# RiskChemi_Monitor_V1_04.net
KiCad netlist of a schematic drawn in Altium Designer
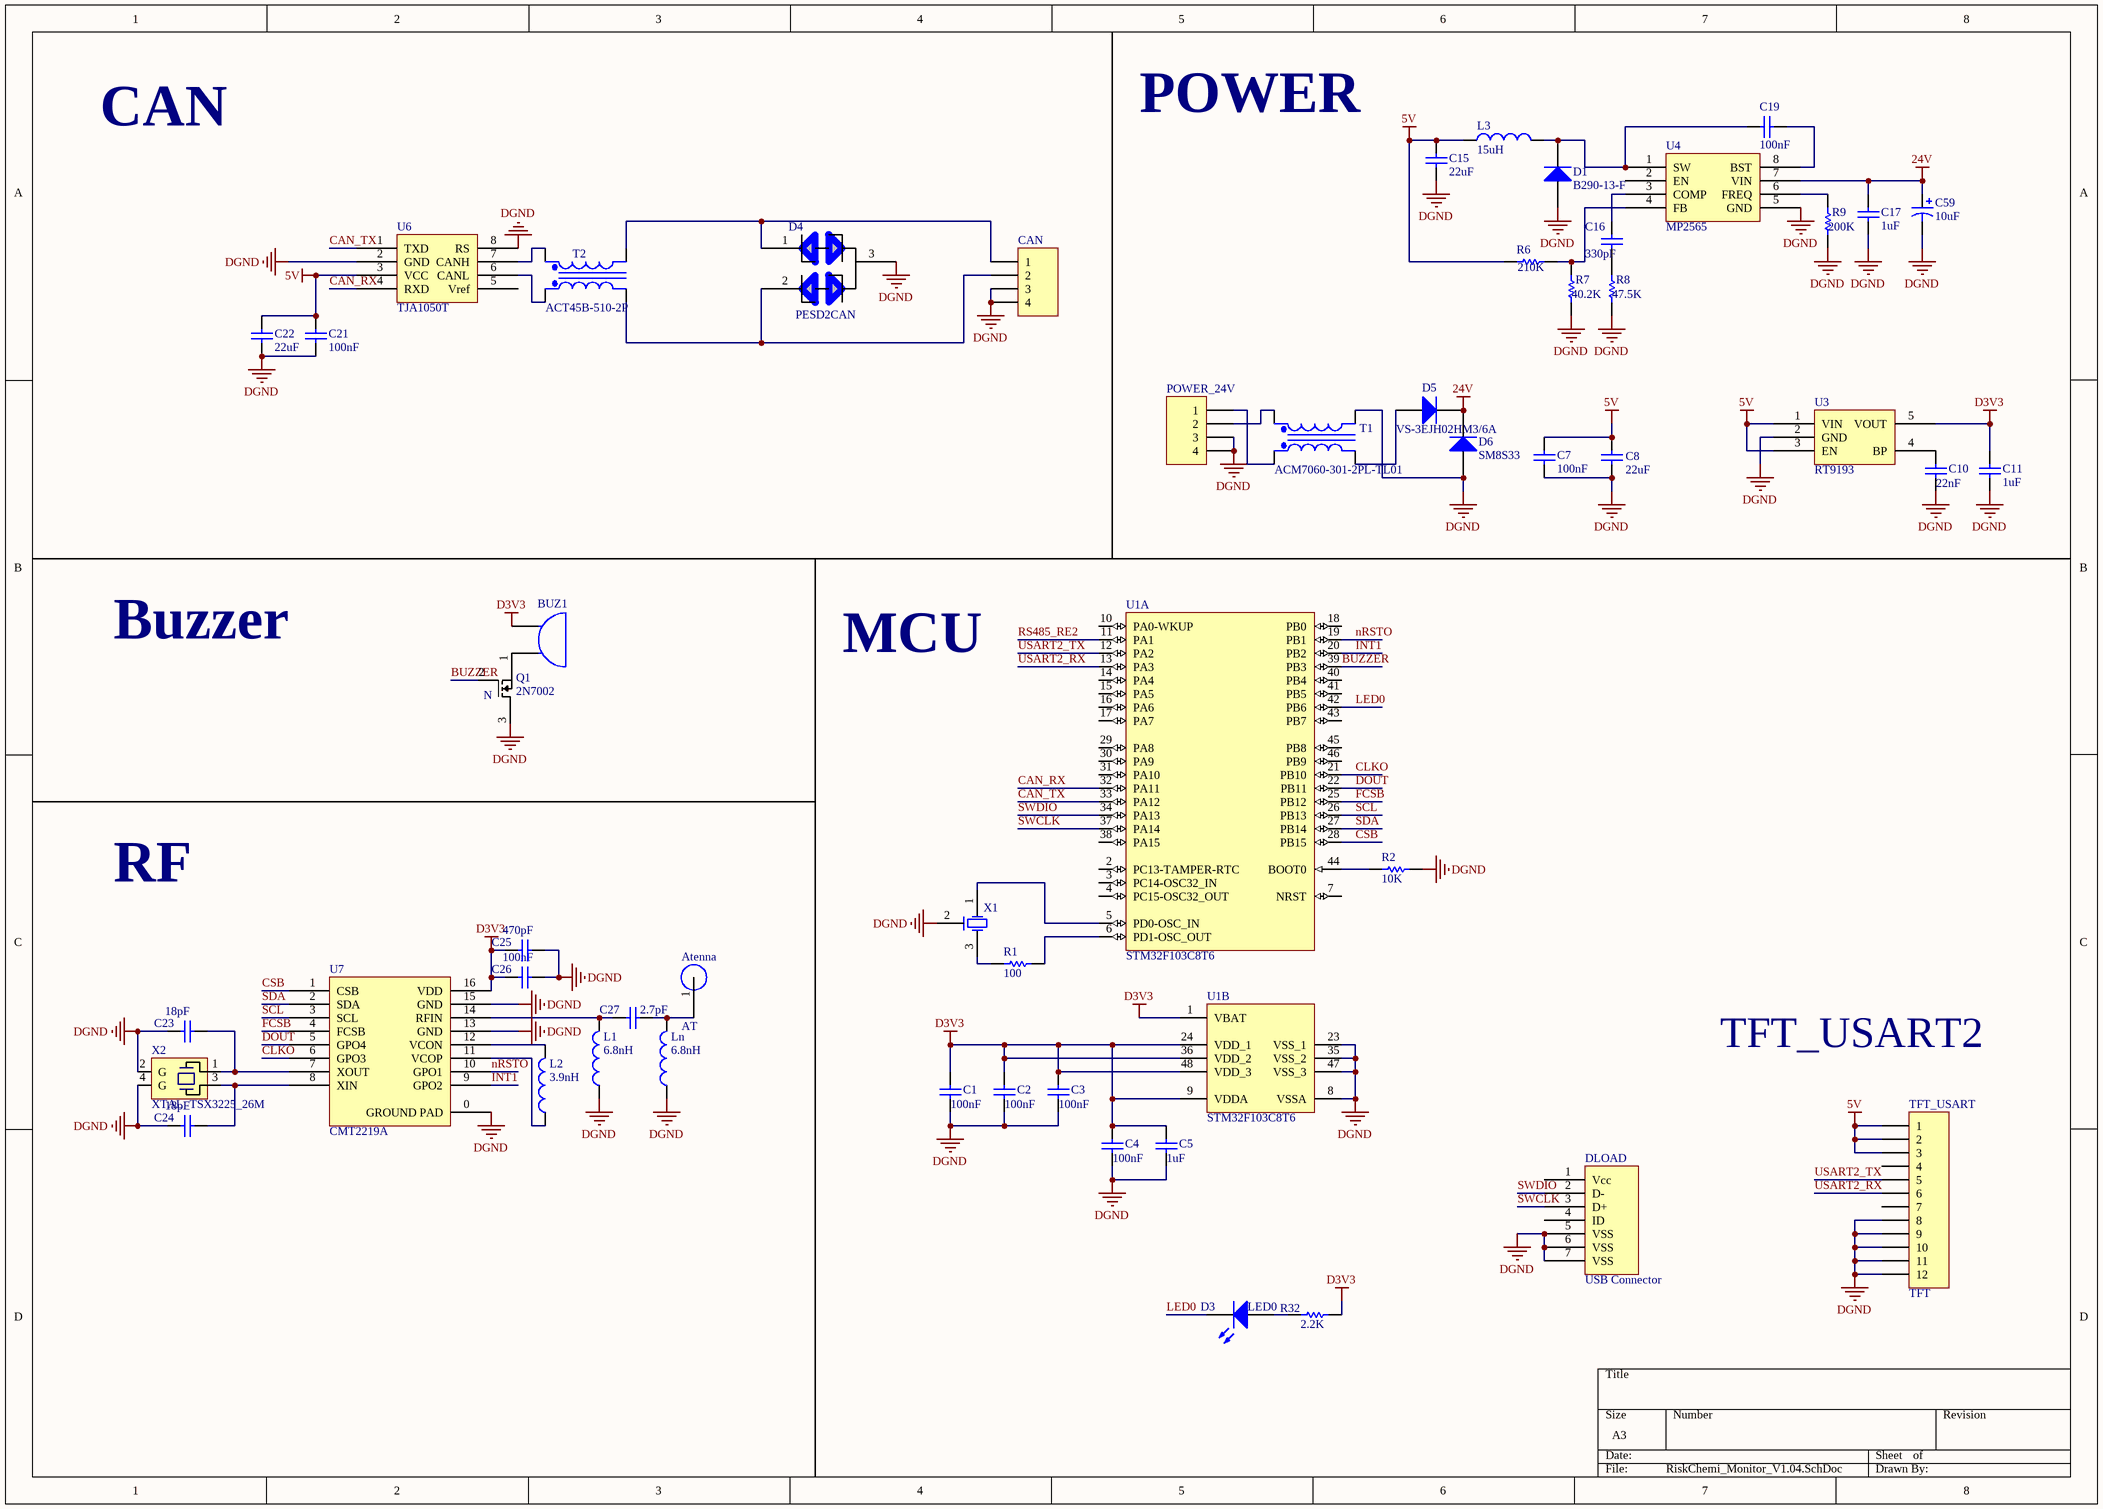
[diagram p0: RiskChemi_Monitor_V1.04.SchDoc]

(export (version "E")
  (design (tool "Eeschema 10.0.6"))
  (components
    (comp (ref "Atenna") (value "AT") (footprint "433MHz Atenna") (libsource (lib "MySchlib1") (part "AT")))
    (comp (ref "BUZ1")
      (value "BUZZER")
      (footprint "BUZ0905")
      (description "Buzzer")
      (libsource (lib "杂元件库") (part "BUZZER"))
    )
    (comp (ref "C1")
      (value "100nF")
      (footprint "0603")
      (description "Capacitor")
      (fields (field (name "PUBLISHER") "Altium Limited"))
      (libsource (lib "Miscellaneous Devices") (part "Cap"))
    )
    (comp (ref "C2")
      (value "100nF")
      (footprint "0603")
      (description "Capacitor")
      (fields (field (name "PUBLISHER") "Altium Limited"))
      (libsource (lib "Miscellaneous Devices") (part "Cap"))
    )
    (comp (ref "C3")
      (value "100nF")
      (footprint "0603")
      (description "Capacitor")
      (fields (field (name "PUBLISHER") "Altium Limited"))
      (libsource (lib "Miscellaneous Devices") (part "Cap"))
    )
    (comp (ref "C4")
      (value "100nF")
      (footprint "0603")
      (description "Capacitor")
      (fields (field (name "PUBLISHER") "Altium Limited"))
      (libsource (lib "Miscellaneous Devices") (part "Cap"))
    )
    (comp (ref "C5")
      (value "1uF")
      (footprint "0603")
      (description "Capacitor")
      (fields (field (name "PUBLISHER") "Altium Limited"))
      (libsource (lib "Miscellaneous Devices") (part "Cap"))
    )
    (comp (ref "C7")
      (value "100nF")
      (footprint "0805")
      (description "Capacitor,100V")
      (fields (field (name "PUBLISHER") "Altium Limited"))
      (libsource (lib "Miscellaneous Devices") (part "Cap"))
    )
    (comp (ref "C8")
      (value "22uF")
      (footprint "0805")
      (description "Capacitor")
      (fields (field (name "PUBLISHER") "Altium Limited"))
      (libsource (lib "Miscellaneous Devices") (part "Cap"))
    )
    (comp (ref "C10")
      (value "22nF")
      (footprint "BinFeng:0603")
      (description "Capacitor")
      (fields (field (name "PUBLISHER") "Altium Limited"))
      (libsource (lib "Miscellaneous Devices") (part "Cap"))
    )
    (comp (ref "C11")
      (value "1uF")
      (footprint "BinFeng:0603")
      (description "Capacitor")
      (fields (field (name "PUBLISHER") "Altium Limited"))
      (libsource (lib "Miscellaneous Devices") (part "Cap"))
    )
    (comp (ref "C15")
      (value "22uF")
      (footprint "0805")
      (description "Capacitor,50V")
      (fields (field (name "PUBLISHER") "Altium Limited"))
      (libsource (lib "Miscellaneous Devices") (part "Cap"))
    )
    (comp (ref "C16")
      (value "330pF")
      (footprint "BinFeng:0402")
      (description "Capacitor")
      (fields (field (name "PUBLISHER") "Altium Limited"))
      (libsource (lib "Miscellaneous Devices") (part "Cap"))
    )
    (comp (ref "C17")
      (value "1uF")
      (footprint "0805")
      (description "Capacitor,100V")
      (fields (field (name "PUBLISHER") "Altium Limited"))
      (libsource (lib "Miscellaneous Devices") (part "Cap"))
    )
    (comp (ref "C19")
      (value "100nF")
      (footprint "BinFeng:0402")
      (description "Capacitor")
      (fields (field (name "PUBLISHER") "Altium Limited"))
      (libsource (lib "Miscellaneous Devices") (part "Cap"))
    )
    (comp (ref "C21")
      (value "100nF")
      (footprint "0603")
      (description "Capacitor")
      (fields (field (name "PUBLISHER") "Altium Limited"))
      (libsource (lib "Miscellaneous Devices") (part "Cap"))
    )
    (comp (ref "C22")
      (value "22uF")
      (footprint "0805")
      (description "Capacitor")
      (fields (field (name "PUBLISHER") "Altium Limited"))
      (libsource (lib "Miscellaneous Devices") (part "Cap"))
    )
    (comp (ref "C23")
      (value "18pF")
      (footprint "BinFeng:0402")
      (description "Capacitor")
      (fields (field (name "PUBLISHER") "Altium Limited"))
      (libsource (lib "Miscellaneous Devices") (part "Cap"))
    )
    (comp (ref "C24")
      (value "18pF")
      (footprint "BinFeng:0402")
      (description "Capacitor")
      (fields (field (name "PUBLISHER") "Altium Limited"))
      (libsource (lib "Miscellaneous Devices") (part "Cap"))
    )
    (comp (ref "C25")
      (value "470pF")
      (footprint "BinFeng:0402")
      (description "Capacitor")
      (fields (field (name "PUBLISHER") "Altium Limited"))
      (libsource (lib "Miscellaneous Devices") (part "Cap"))
    )
    (comp (ref "C26")
      (value "100nF")
      (footprint "BinFeng:0603")
      (description "Capacitor")
      (fields (field (name "PUBLISHER") "Altium Limited"))
      (libsource (lib "Miscellaneous Devices") (part "Cap"))
    )
    (comp (ref "C27")
      (value "2.7pF")
      (footprint "BinFeng:nosilk_0402")
      (description "Capacitor")
      (fields (field (name "PUBLISHER") "Altium Limited"))
      (libsource (lib "Miscellaneous Devices") (part "Cap"))
    )
    (comp (ref "C59")
      (value "10uF")
      (footprint "6032_pol")
      (description "Polarized Capacitor (Radial)")
      (fields (field (name "PUBLISHER") "Altium Limited"))
      (libsource (lib "Miscellaneous Devices") (part "Cap Pol1"))
    )
    (comp (ref "CAN")
      (value "Header 4")
      (footprint "C3000VS")
      (description "Header, 4-Pin")
      (fields (field (name "PUBLISHER") "Altium Limited"))
      (libsource (lib "") (part "Header 4_1"))
    )
    (comp (ref "D1")
      (value "B290-13-F")
      (footprint "back:B290")
      (description "Default Diode")
      (fields (field (name "PUBLISHER") "Altium Limited"))
      (libsource (lib "Miscellaneous Devices") (part "Diode"))
    )
    (comp (ref "D3")
      (value "LED0")
      (footprint "LED")
      (description "green LED")
      (fields (field (name "PUBLISHER") "Altium Limited"))
      (libsource (lib "Miscellaneous Devices") (part "LED0"))
    )
    (comp (ref "D4")
      (value "PESD2CAN")
      (footprint "SOT23")
      (libsource (lib "BinFeng_Connectors") (part "PESD1CAN"))
    )
    (comp (ref "D5")
      (value "VS-3EJH02HM3/6A")
      (footprint "back:B290")
      (description "1 Amp General Purpose Rectifier")
      (fields (field (name "PUBLISHER") "Altium Limited"))
      (libsource (lib "Miscellaneous Devices") (part "Diode 1N4007"))
    )
    (comp (ref "D6")
      (value "SM8S33")
      (footprint "SM8S")
      (description "1 Amp General Purpose Rectifier")
      (fields (field (name "PUBLISHER") "Altium Limited"))
      (libsource (lib "Miscellaneous Devices") (part "Diode 1N4007"))
    )
    (comp (ref "DLOAD")
      (value "USB Connector")
      (footprint "Mini_USB")
      (libsource (lib "BinFeng_Connectors") (part "Component_1"))
    )
    (comp (ref "L1")
      (value "6.8nH")
      (footprint "Miscellaneous Devices:0402")
      (description "Inductor")
      (fields (field (name "PUBLISHER") "Altium Limited"))
      (libsource (lib "Miscellaneous Devices") (part "Inductor"))
    )
    (comp (ref "L2")
      (value "3.9nH")
      (footprint "BinFeng:0603")
      (description "Inductor")
      (fields (field (name "PUBLISHER") "Altium Limited"))
      (libsource (lib "Miscellaneous Devices") (part "Inductor"))
    )
    (comp (ref "L3")
      (value "15uH")
      (footprint "4*4 Inductor")
      (description "Inductor, 1A")
      (fields (field (name "PUBLISHER") "Altium Limited"))
      (libsource (lib "Miscellaneous Devices") (part "Inductor"))
    )
    (comp (ref "Ln")
      (value "6.8nH")
      (footprint "Miscellaneous Devices:0402")
      (description "Inductor")
      (fields (field (name "PUBLISHER") "Altium Limited"))
      (libsource (lib "Miscellaneous Devices") (part "Inductor"))
    )
    (comp (ref "POWER_24V")
      (value "Header 4")
      (footprint "C3000VS")
      (description "Header, 4-Pin")
      (fields (field (name "PUBLISHER") "Altium Limited"))
      (libsource (lib "Miscellaneous Connectors") (part "Header 4"))
    )
    (comp (ref "Q1") (value "2N7002") (footprint "2N7002") (libsource (lib "seeder") (part "N-MOSFET")))
    (comp (ref "R1")
      (value "100")
      (footprint "back:0603")
      (description "Resistor")
      (fields (field (name "PUBLISHER") "Altium Limited"))
      (libsource (lib "Miscellaneous Devices") (part "Res1"))
    )
    (comp (ref "R2")
      (value "10K")
      (footprint "back:0603")
      (description "Resistor")
      (fields (field (name "PUBLISHER") "Altium Limited"))
      (libsource (lib "Miscellaneous Devices") (part "Res1"))
    )
    (comp (ref "R6")
      (value "210K")
      (footprint "BinFeng:0402")
      (description "Resistor")
      (fields (field (name "PUBLISHER") "Altium Limited"))
      (libsource (lib "Miscellaneous Devices") (part "Res1"))
    )
    (comp (ref "R7")
      (value "40.2K")
      (footprint "BinFeng:0402")
      (description "Resistor")
      (fields (field (name "PUBLISHER") "Altium Limited"))
      (libsource (lib "Miscellaneous Devices") (part "Res1"))
    )
    (comp (ref "R8")
      (value "47.5K")
      (footprint "BinFeng:0402")
      (description "Resistor")
      (fields (field (name "PUBLISHER") "Altium Limited"))
      (libsource (lib "Miscellaneous Devices") (part "Res1"))
    )
    (comp (ref "R9")
      (value "200K")
      (footprint "BinFeng:0402")
      (description "Resistor")
      (fields (field (name "PUBLISHER") "Altium Limited"))
      (libsource (lib "Miscellaneous Devices") (part "Res1"))
    )
    (comp (ref "R32")
      (value "2.2K")
      (footprint "BinFeng:0603")
      (description "Resistor")
      (fields (field (name "PUBLISHER") "Altium Limited"))
      (libsource (lib "Miscellaneous Devices") (part "Res1"))
    )
    (comp (ref "T1")
      (value "ACM7060-301-2PL-TL01")
      (footprint "ACM7060-301-2P-TL01")
      (description "Transformer (Equivalent Circuit Model)")
      (fields (field (name "PUBLISHER") "Altium Limited"))
      (libsource (lib "Miscellaneous Devices") (part "Trans Eq"))
    )
    (comp (ref "T2")
      (value "ACT45B-510-2P")
      (footprint "ACT45B-510-2P")
      (description "Transformer (Equivalent Circuit Model)")
      (fields (field (name "PUBLISHER") "Altium Limited"))
      (libsource (lib "Miscellaneous Devices") (part "Trans Eq"))
    )
    (comp (ref "TFT_USART")
      (value "TFT")
      (footprint "FCC_10pin_1mm")
      (description "Header, 12-Pin")
      (fields (field (name "PUBLISHER") "Altium Limited"))
      (libsource (lib "Miscellaneous Connectors") (part "Header 12"))
    )
    (comp (ref "U1")
      (value "STM32F103C8T6")
      (footprint "STM-LQFP48_N")
      (libsource (lib "STMicroelectronics STM32 F1") (part "STM32F103C8T6"))
    )
    (comp (ref "U3") (value "RT9193") (footprint "SOT-23-5") (libsource (lib "BinFeng_IC") (part "RT9193")))
    (comp (ref "U4")
      (value "MP2565")
      (footprint "SO8")
      (description "DCDC 4.5V~28V input 1.8V ~5V output low power")
      (libsource (lib "BinFeng_IC") (part "MP1584"))
    )
    (comp (ref "U6")
      (value "TJA1050T")
      (footprint "SO8")
      (description "CAN Tranceiver")
      (libsource (lib "BinFeng_IC") (part "TJA1050T"))
    )
    (comp (ref "U7")
      (value "CMT2219A")
      (footprint "back:QFN16")
      (libsource (lib "BinFeng_IC") (part "CMT2219A"))
    )
    (comp (ref "X1") (value "8M smd") (footprint "8Mhz_XTAL") (libsource (lib "Schlib1") (part "8M smd")))
    (comp (ref "X2")
      (value "XTAL_TSX3225_26M")
      (footprint "XTAL3225")
      (libsource (lib "BinFeng_IC") (part "XTAL_Negative"))
    )
  )
  (nets
    (net (code "1") (name "/BUZZER") (class "Default")
      (node (ref "Q1") (pin "2") (pinfunction "G_2") (pintype "passive"))
      (node (ref "U1") (pin "39") (pinfunction "PB3_39") (pintype "bidirectional"))
    )
    (net (code "2") (name "/CAN_RX") (class "Default")
      (node (ref "U1") (pin "32") (pinfunction "PA11_32") (pintype "bidirectional"))
      (node (ref "U6") (pin "4") (pinfunction "RXD_4") (pintype "passive"))
    )
    (net (code "3") (name "/CAN_TX") (class "Default")
      (node (ref "U1") (pin "33") (pinfunction "PA12_33") (pintype "bidirectional"))
      (node (ref "U6") (pin "1") (pinfunction "TXD_1") (pintype "passive"))
    )
    (net (code "4") (name "/CLKO") (class "Default")
      (node (ref "U1") (pin "21") (pinfunction "PB10_21") (pintype "bidirectional"))
      (node (ref "U7") (pin "6") (pinfunction "GPO3_6") (pintype "passive"))
    )
    (net (code "5") (name "/CSB") (class "Default")
      (node (ref "U1") (pin "28") (pinfunction "PB15_28") (pintype "bidirectional"))
      (node (ref "U7") (pin "1") (pinfunction "CSB_1") (pintype "passive"))
    )
    (net (code "6") (name "/DOUT") (class "Default")
      (node (ref "U1") (pin "22") (pinfunction "PB11_22") (pintype "bidirectional"))
      (node (ref "U7") (pin "5") (pinfunction "GPO4_5") (pintype "passive"))
    )
    (net (code "7") (name "/FCSB") (class "Default")
      (node (ref "U1") (pin "25") (pinfunction "PB12_25") (pintype "bidirectional"))
      (node (ref "U7") (pin "4") (pinfunction "FCSB_4") (pintype "passive"))
    )
    (net (code "8") (name "/INT1") (class "Default")
      (node (ref "U1") (pin "20") (pinfunction "PB2_20") (pintype "bidirectional"))
      (node (ref "U7") (pin "9") (pinfunction "GPO2_9") (pintype "passive"))
    )
    (net (code "9") (name "/LED0") (class "Default")
      (node (ref "D3") (pin "2") (pinfunction "K_2") (pintype "passive"))
      (node (ref "U1") (pin "42") (pinfunction "PB6_42") (pintype "bidirectional"))
    )
    (net (code "10") (name "/RS485_RE2") (class "Default")
      (node (ref "U1") (pin "11") (pinfunction "PA1_11") (pintype "bidirectional"))
    )
    (net (code "11") (name "/SCL") (class "Default")
      (node (ref "U1") (pin "26") (pinfunction "PB13_26") (pintype "bidirectional"))
      (node (ref "U7") (pin "3") (pinfunction "SCL_3") (pintype "passive"))
    )
    (net (code "12") (name "/SDA") (class "Default")
      (node (ref "U1") (pin "27") (pinfunction "PB14_27") (pintype "bidirectional"))
      (node (ref "U7") (pin "2") (pinfunction "SDA_2") (pintype "passive"))
    )
    (net (code "13") (name "/SWCLK") (class "Default")
      (node (ref "DLOAD") (pin "3") (pinfunction "D+_3") (pintype "passive"))
      (node (ref "U1") (pin "37") (pinfunction "PA14_37") (pintype "bidirectional"))
    )
    (net (code "14") (name "/SWDIO") (class "Default")
      (node (ref "DLOAD") (pin "2") (pinfunction "D-_2") (pintype "passive"))
      (node (ref "U1") (pin "34") (pinfunction "PA13_34") (pintype "bidirectional"))
    )
    (net (code "15") (name "/USART2_RX") (class "Default")
      (node (ref "TFT_USART") (pin "6") (pinfunction "6_6") (pintype "passive"))
      (node (ref "U1") (pin "13") (pinfunction "PA3_13") (pintype "bidirectional"))
    )
    (net (code "16") (name "/USART2_TX") (class "Default")
      (node (ref "TFT_USART") (pin "5") (pinfunction "5_5") (pintype "passive"))
      (node (ref "U1") (pin "12") (pinfunction "PA2_12") (pintype "bidirectional"))
    )
    (net (code "17") (name "/nRSTO") (class "Default")
      (node (ref "U1") (pin "19") (pinfunction "PB1_19") (pintype "bidirectional"))
      (node (ref "U7") (pin "10") (pinfunction "GPO1_10") (pintype "passive"))
    )
    (net (code "18") (name "5V") (class "Default")
      (node (ref "C15") (pin "2") (pinfunction "2_2") (pintype "passive"))
      (node (ref "C21") (pin "1") (pinfunction "1_1") (pintype "passive"))
      (node (ref "C22") (pin "2") (pinfunction "2_2") (pintype "passive"))
      (node (ref "C7") (pin "2") (pinfunction "2_2") (pintype "passive"))
      (node (ref "C8") (pin "2") (pinfunction "2_2") (pintype "passive"))
      (node (ref "L3") (pin "1") (pinfunction "1_1") (pintype "passive"))
      (node (ref "R6") (pin "2") (pinfunction "2_2") (pintype "passive"))
      (node (ref "TFT_USART") (pin "1") (pinfunction "1_1") (pintype "passive"))
      (node (ref "TFT_USART") (pin "2") (pinfunction "2_2") (pintype "passive"))
      (node (ref "TFT_USART") (pin "3") (pinfunction "3_3") (pintype "passive"))
      (node (ref "U3") (pin "1") (pinfunction "VIN_1") (pintype "passive"))
      (node (ref "U3") (pin "3") (pinfunction "EN_3") (pintype "passive"))
      (node (ref "U6") (pin "3") (pinfunction "VCC_3") (pintype "passive"))
    )
    (net (code "19") (name "24V") (class "Default")
      (node (ref "C17") (pin "2") (pinfunction "2_2") (pintype "passive"))
      (node (ref "C59") (pin "1") (pinfunction "1_1") (pintype "passive"))
      (node (ref "D5") (pin "2") (pinfunction "K_2") (pintype "passive"))
      (node (ref "D6") (pin "2") (pinfunction "K_2") (pintype "passive"))
      (node (ref "U4") (pin "7") (pinfunction "VIN_7") (pintype "passive"))
    )
    (net (code "20") (name "D3V3") (class "Default")
      (node (ref "BUZ1") (pin "1") (pinfunction "A_1") (pintype "passive"))
      (node (ref "C1") (pin "2") (pinfunction "2_2") (pintype "passive"))
      (node (ref "C11") (pin "2") (pinfunction "2_2") (pintype "passive"))
      (node (ref "C2") (pin "2") (pinfunction "2_2") (pintype "passive"))
      (node (ref "C25") (pin "2") (pinfunction "2_2") (pintype "passive"))
      (node (ref "C26") (pin "2") (pinfunction "2_2") (pintype "passive"))
      (node (ref "C3") (pin "2") (pinfunction "2_2") (pintype "passive"))
      (node (ref "C4") (pin "2") (pinfunction "2_2") (pintype "passive"))
      (node (ref "C5") (pin "2") (pinfunction "2_2") (pintype "passive"))
      (node (ref "R32") (pin "1") (pinfunction "1_1") (pintype "passive"))
      (node (ref "U1") (pin "1") (pinfunction "VBAT_1") (pintype "power_in"))
      (node (ref "U1") (pin "24") (pinfunction "VDD_1_24") (pintype "power_in"))
      (node (ref "U1") (pin "36") (pinfunction "VDD_2_36") (pintype "power_in"))
      (node (ref "U1") (pin "48") (pinfunction "VDD_3_48") (pintype "power_in"))
      (node (ref "U1") (pin "9") (pinfunction "VDDA_9") (pintype "power_in"))
      (node (ref "U3") (pin "5") (pinfunction "VOUT_5") (pintype "passive"))
      (node (ref "U7") (pin "16") (pinfunction "VDD_16") (pintype "passive"))
    )
    (net (code "21") (name "DGND") (class "Default")
      (node (ref "C1") (pin "1") (pinfunction "1_1") (pintype "passive"))
      (node (ref "C10") (pin "1") (pinfunction "1_1") (pintype "passive"))
      (node (ref "C11") (pin "1") (pinfunction "1_1") (pintype "passive"))
      (node (ref "C15") (pin "1") (pinfunction "1_1") (pintype "passive"))
      (node (ref "C17") (pin "1") (pinfunction "1_1") (pintype "passive"))
      (node (ref "C2") (pin "1") (pinfunction "1_1") (pintype "passive"))
      (node (ref "C21") (pin "2") (pinfunction "2_2") (pintype "passive"))
      (node (ref "C22") (pin "1") (pinfunction "1_1") (pintype "passive"))
      (node (ref "C23") (pin "2") (pinfunction "2_2") (pintype "passive"))
      (node (ref "C24") (pin "2") (pinfunction "2_2") (pintype "passive"))
      (node (ref "C25") (pin "1") (pinfunction "1_1") (pintype "passive"))
      (node (ref "C26") (pin "1") (pinfunction "1_1") (pintype "passive"))
      (node (ref "C3") (pin "1") (pinfunction "1_1") (pintype "passive"))
      (node (ref "C4") (pin "1") (pinfunction "1_1") (pintype "passive"))
      (node (ref "C5") (pin "1") (pinfunction "1_1") (pintype "passive"))
      (node (ref "C59") (pin "2") (pinfunction "2_2") (pintype "passive"))
      (node (ref "C7") (pin "1") (pinfunction "1_1") (pintype "passive"))
      (node (ref "C8") (pin "1") (pinfunction "1_1") (pintype "passive"))
      (node (ref "CAN") (pin "3") (pinfunction "3_3") (pintype "passive"))
      (node (ref "CAN") (pin "4") (pinfunction "4_4") (pintype "passive"))
      (node (ref "D1") (pin "1") (pinfunction "A_1") (pintype "passive"))
      (node (ref "D4") (pin "3") (pinfunction "13_3") (pintype "passive"))
      (node (ref "D6") (pin "1") (pinfunction "A_1") (pintype "passive"))
      (node (ref "DLOAD") (pin "5") (pinfunction "VSS_5") (pintype "passive"))
      (node (ref "DLOAD") (pin "6") (pinfunction "VSS_6") (pintype "passive"))
      (node (ref "DLOAD") (pin "7") (pinfunction "VSS_7") (pintype "passive"))
      (node (ref "L1") (pin "1") (pinfunction "1_1") (pintype "passive"))
      (node (ref "Ln") (pin "1") (pinfunction "1_1") (pintype "passive"))
      (node (ref "POWER_24V") (pin "3") (pinfunction "3_3") (pintype "passive"))
      (node (ref "POWER_24V") (pin "4") (pinfunction "4_4") (pintype "passive"))
      (node (ref "Q1") (pin "3") (pinfunction "S_3") (pintype "passive"))
      (node (ref "R2") (pin "2") (pinfunction "2_2") (pintype "passive"))
      (node (ref "R7") (pin "1") (pinfunction "1_1") (pintype "passive"))
      (node (ref "R8") (pin "1") (pinfunction "1_1") (pintype "passive"))
      (node (ref "R9") (pin "1") (pinfunction "1_1") (pintype "passive"))
      (node (ref "T1") (pin "4") (pinfunction "Sec-_4") (pintype "passive"))
      (node (ref "TFT_USART") (pin "10") (pinfunction "10_10") (pintype "passive"))
      (node (ref "TFT_USART") (pin "11") (pinfunction "11_11") (pintype "passive"))
      (node (ref "TFT_USART") (pin "12") (pinfunction "12_12") (pintype "passive"))
      (node (ref "TFT_USART") (pin "8") (pinfunction "8_8") (pintype "passive"))
      (node (ref "TFT_USART") (pin "9") (pinfunction "9_9") (pintype "passive"))
      (node (ref "U1") (pin "23") (pinfunction "VSS_1_23") (pintype "power_in"))
      (node (ref "U1") (pin "35") (pinfunction "VSS_2_35") (pintype "power_in"))
      (node (ref "U1") (pin "47") (pinfunction "VSS_3_47") (pintype "power_in"))
      (node (ref "U1") (pin "8") (pinfunction "VSSA_8") (pintype "power_in"))
      (node (ref "U3") (pin "2") (pinfunction "GND_2") (pintype "passive"))
      (node (ref "U4") (pin "5") (pinfunction "GND_5") (pintype "passive"))
      (node (ref "U6") (pin "2") (pinfunction "GND_2") (pintype "passive"))
      (node (ref "U6") (pin "8") (pinfunction "RS_8") (pintype "passive"))
      (node (ref "U7") (pin "0") (pinfunction "GROUND_PAD_0") (pintype "passive"))
      (node (ref "U7") (pin "13") (pinfunction "GND_13") (pintype "passive"))
      (node (ref "U7") (pin "15") (pinfunction "GND_15") (pintype "passive"))
      (node (ref "X1") (pin "2") (pinfunction "GND_2") (pintype "passive"))
      (node (ref "X2") (pin "2") (pinfunction "G_2") (pintype "passive"))
      (node (ref "X2") (pin "4") (pinfunction "G_4") (pintype "passive"))
    )
    (net (code "22") (name "Net-(Atenna-Pad1)") (class "Default")
      (node (ref "Atenna") (pin "1") (pinfunction "1_1") (pintype "passive"))
      (node (ref "C27") (pin "1") (pinfunction "1_1") (pintype "passive"))
      (node (ref "Ln") (pin "2") (pinfunction "2_2") (pintype "passive"))
    )
    (net (code "23") (name "Net-(BUZ1-B)") (class "Default")
      (node (ref "BUZ1") (pin "2") (pinfunction "B_2") (pintype "passive"))
      (node (ref "Q1") (pin "1") (pinfunction "D_1") (pintype "passive"))
    )
    (net (code "24") (name "Net-(C16-Pad2)") (class "Default")
      (node (ref "C16") (pin "2") (pinfunction "2_2") (pintype "passive"))
      (node (ref "R8") (pin "2") (pinfunction "2_2") (pintype "passive"))
    )
    (net (code "25") (name "Net-(D1-K)") (class "Default")
      (node (ref "C19") (pin "2") (pinfunction "2_2") (pintype "passive"))
      (node (ref "D1") (pin "2") (pinfunction "K_2") (pintype "passive"))
      (node (ref "L3") (pin "2") (pinfunction "2_2") (pintype "passive"))
      (node (ref "U4") (pin "1") (pinfunction "SW_1") (pintype "passive"))
    )
    (net (code "26") (name "Net-(D3-A)") (class "Default")
      (node (ref "D3") (pin "1") (pinfunction "A_1") (pintype "passive"))
      (node (ref "R32") (pin "2") (pinfunction "2_2") (pintype "passive"))
    )
    (net (code "27") (name "Net-(D4-11)") (class "Default")
      (node (ref "CAN") (pin "1") (pinfunction "1_1") (pintype "passive"))
      (node (ref "D4") (pin "1") (pinfunction "11_1") (pintype "passive"))
      (node (ref "T2") (pin "4") (pinfunction "Sec-_4") (pintype "passive"))
    )
    (net (code "28") (name "Net-(D4-12)") (class "Default")
      (node (ref "CAN") (pin "2") (pinfunction "2_2") (pintype "passive"))
      (node (ref "D4") (pin "2") (pinfunction "12_2") (pintype "passive"))
      (node (ref "T2") (pin "2") (pinfunction "Pri-_2") (pintype "passive"))
    )
    (net (code "29") (name "Net-(D5-A)") (class "Default")
      (node (ref "D5") (pin "1") (pinfunction "A_1") (pintype "passive"))
      (node (ref "T1") (pin "2") (pinfunction "Pri-_2") (pintype "passive"))
    )
    (net (code "30") (name "Net-(T1-Pri+)") (class "Default")
      (node (ref "POWER_24V") (pin "1") (pinfunction "1_1") (pintype "passive"))
      (node (ref "T1") (pin "1") (pinfunction "Pri+_1") (pintype "passive"))
    )
    (net (code "31") (name "Net-(T1-Sec+)") (class "Default")
      (node (ref "POWER_24V") (pin "2") (pinfunction "2_2") (pintype "passive"))
      (node (ref "T1") (pin "3") (pinfunction "Sec+_3") (pintype "passive"))
    )
    (net (code "32") (name "Net-(T2-Pri+)") (class "Default")
      (node (ref "T2") (pin "1") (pinfunction "Pri+_1") (pintype "passive"))
      (node (ref "U6") (pin "6") (pinfunction "CANL_6") (pintype "passive"))
    )
    (net (code "33") (name "Net-(T2-Sec+)") (class "Default")
      (node (ref "T2") (pin "3") (pinfunction "Sec+_3") (pintype "passive"))
      (node (ref "U6") (pin "7") (pinfunction "CANH_7") (pintype "passive"))
    )
    (net (code "34") (name "Net-(U1A-BOOT0)") (class "Default")
      (node (ref "R2") (pin "1") (pinfunction "1_1") (pintype "passive"))
      (node (ref "U1") (pin "44") (pinfunction "BOOT0_44") (pintype "input"))
    )
    (net (code "35") (name "Net-(U1A-PD0-OSC_IN)") (class "Default")
      (node (ref "U1") (pin "5") (pinfunction "PD0-OSC_IN_5") (pintype "bidirectional"))
      (node (ref "X1") (pin "1") (pinfunction "OSC1_1") (pintype "passive"))
    )
    (net (code "36") (name "Net-(U1A-PD1-OSC_OUT)") (class "Default")
      (node (ref "R1") (pin "2") (pinfunction "2_2") (pintype "passive"))
      (node (ref "U1") (pin "6") (pinfunction "PD1-OSC_OUT_6") (pintype "bidirectional"))
    )
    (net (code "37") (name "Net-(U3-BP)") (class "Default")
      (node (ref "C10") (pin "2") (pinfunction "2_2") (pintype "passive"))
      (node (ref "U3") (pin "4") (pinfunction "BP_4") (pintype "passive"))
    )
    (net (code "38") (name "Net-(U4-BST)") (class "Default")
      (node (ref "C19") (pin "1") (pinfunction "1_1") (pintype "passive"))
      (node (ref "U4") (pin "8") (pinfunction "BST_8") (pintype "passive"))
    )
    (net (code "39") (name "Net-(U4-COMP)") (class "Default")
      (node (ref "C16") (pin "1") (pinfunction "1_1") (pintype "passive"))
      (node (ref "U4") (pin "3") (pinfunction "COMP_3") (pintype "passive"))
    )
    (net (code "40") (name "Net-(U4-FB)") (class "Default")
      (node (ref "R6") (pin "1") (pinfunction "1_1") (pintype "passive"))
      (node (ref "R7") (pin "2") (pinfunction "2_2") (pintype "passive"))
      (node (ref "U4") (pin "4") (pinfunction "FB_4") (pintype "passive"))
    )
    (net (code "41") (name "Net-(U4-FREQ)") (class "Default")
      (node (ref "R9") (pin "2") (pinfunction "2_2") (pintype "passive"))
      (node (ref "U4") (pin "6") (pinfunction "FREQ_6") (pintype "passive"))
    )
    (net (code "42") (name "Net-(U7-RFIN)") (class "Default")
      (node (ref "C27") (pin "2") (pinfunction "2_2") (pintype "passive"))
      (node (ref "L1") (pin "2") (pinfunction "2_2") (pintype "passive"))
      (node (ref "U7") (pin "14") (pinfunction "RFIN_14") (pintype "passive"))
    )
    (net (code "43") (name "Net-(U7-VCON)") (class "Default")
      (node (ref "L2") (pin "2") (pinfunction "2_2") (pintype "passive"))
      (node (ref "U7") (pin "12") (pinfunction "VCON_12") (pintype "passive"))
    )
    (net (code "44") (name "Net-(U7-VCOP)") (class "Default")
      (node (ref "L2") (pin "1") (pinfunction "1_1") (pintype "passive"))
      (node (ref "U7") (pin "11") (pinfunction "VCOP_11") (pintype "passive"))
    )
    (net (code "45") (name "Net-(U7-XIN)") (class "Default")
      (node (ref "C24") (pin "1") (pinfunction "1_1") (pintype "passive"))
      (node (ref "U7") (pin "8") (pinfunction "XIN_8") (pintype "passive"))
      (node (ref "X2") (pin "3") (pintype "passive"))
    )
    (net (code "46") (name "Net-(U7-XOUT)") (class "Default")
      (node (ref "C23") (pin "1") (pinfunction "1_1") (pintype "passive"))
      (node (ref "U7") (pin "7") (pinfunction "XOUT_7") (pintype "passive"))
      (node (ref "X2") (pin "1") (pintype "passive"))
    )
    (net (code "47") (name "Net-(X1-OSC2)") (class "Default")
      (node (ref "R1") (pin "1") (pinfunction "1_1") (pintype "passive"))
      (node (ref "X1") (pin "3") (pinfunction "OSC2_3") (pintype "passive"))
    )
    (net (code "48") (name "unconnected-(DLOAD-ID-Pad4)") (class "Default")
      (node (ref "DLOAD") (pin "4") (pinfunction "ID_4") (pintype "passive"))
    )
    (net (code "49") (name "unconnected-(DLOAD-Vcc-Pad1)") (class "Default")
      (node (ref "DLOAD") (pin "1") (pinfunction "Vcc_1") (pintype "passive"))
    )
    (net (code "50") (name "unconnected-(TFT_USART-Pad4)") (class "Default")
      (node (ref "TFT_USART") (pin "4") (pinfunction "4_4") (pintype "passive"))
    )
    (net (code "51") (name "unconnected-(TFT_USART-Pad7)") (class "Default")
      (node (ref "TFT_USART") (pin "7") (pinfunction "7_7") (pintype "passive"))
    )
    (net (code "52") (name "unconnected-(U1A-NRST-Pad7)") (class "Default")
      (node (ref "U1") (pin "7") (pinfunction "NRST_7") (pintype "bidirectional"))
    )
    (net (code "53") (name "unconnected-(U1A-PA0-WKUP-Pad10)") (class "Default")
      (node (ref "U1") (pin "10") (pinfunction "PA0-WKUP_10") (pintype "bidirectional"))
    )
    (net (code "54") (name "unconnected-(U1A-PA4-Pad14)") (class "Default")
      (node (ref "U1") (pin "14") (pinfunction "PA4_14") (pintype "bidirectional"))
    )
    (net (code "55") (name "unconnected-(U1A-PA5-Pad15)") (class "Default")
      (node (ref "U1") (pin "15") (pinfunction "PA5_15") (pintype "bidirectional"))
    )
    (net (code "56") (name "unconnected-(U1A-PA6-Pad16)") (class "Default")
      (node (ref "U1") (pin "16") (pinfunction "PA6_16") (pintype "bidirectional"))
    )
    (net (code "57") (name "unconnected-(U1A-PA7-Pad17)") (class "Default")
      (node (ref "U1") (pin "17") (pinfunction "PA7_17") (pintype "bidirectional"))
    )
    (net (code "58") (name "unconnected-(U1A-PA8-Pad29)") (class "Default")
      (node (ref "U1") (pin "29") (pinfunction "PA8_29") (pintype "bidirectional"))
    )
    (net (code "59") (name "unconnected-(U1A-PA9-Pad30)") (class "Default")
      (node (ref "U1") (pin "30") (pinfunction "PA9_30") (pintype "bidirectional"))
    )
    (net (code "60") (name "unconnected-(U1A-PA10-Pad31)") (class "Default")
      (node (ref "U1") (pin "31") (pinfunction "PA10_31") (pintype "bidirectional"))
    )
    (net (code "61") (name "unconnected-(U1A-PA15-Pad38)") (class "Default")
      (node (ref "U1") (pin "38") (pinfunction "PA15_38") (pintype "bidirectional"))
    )
    (net (code "62") (name "unconnected-(U1A-PB0-Pad18)") (class "Default")
      (node (ref "U1") (pin "18") (pinfunction "PB0_18") (pintype "bidirectional"))
    )
    (net (code "63") (name "unconnected-(U1A-PB4-Pad40)") (class "Default")
      (node (ref "U1") (pin "40") (pinfunction "PB4_40") (pintype "bidirectional"))
    )
    (net (code "64") (name "unconnected-(U1A-PB5-Pad41)") (class "Default")
      (node (ref "U1") (pin "41") (pinfunction "PB5_41") (pintype "bidirectional"))
    )
    (net (code "65") (name "unconnected-(U1A-PB7-Pad43)") (class "Default")
      (node (ref "U1") (pin "43") (pinfunction "PB7_43") (pintype "bidirectional"))
    )
    (net (code "66") (name "unconnected-(U1A-PB8-Pad45)") (class "Default")
      (node (ref "U1") (pin "45") (pinfunction "PB8_45") (pintype "bidirectional"))
    )
    (net (code "67") (name "unconnected-(U1A-PB9-Pad46)") (class "Default")
      (node (ref "U1") (pin "46") (pinfunction "PB9_46") (pintype "bidirectional"))
    )
    (net (code "68") (name "unconnected-(U1A-PC13-TAMPER-RTC-Pad2)") (class "Default")
      (node (ref "U1") (pin "2") (pinfunction "PC13-TAMPER-RTC_2") (pintype "bidirectional"))
    )
    (net (code "69") (name "unconnected-(U1A-PC14-OSC32_IN-Pad3)") (class "Default")
      (node (ref "U1") (pin "3") (pinfunction "PC14-OSC32_IN_3") (pintype "bidirectional"))
    )
    (net (code "70") (name "unconnected-(U1A-PC15-OSC32_OUT-Pad4)") (class "Default")
      (node (ref "U1") (pin "4") (pinfunction "PC15-OSC32_OUT_4") (pintype "bidirectional"))
    )
    (net (code "71") (name "unconnected-(U4-EN-Pad2)") (class "Default")
      (node (ref "U4") (pin "2") (pinfunction "EN_2") (pintype "passive"))
    )
    (net (code "72") (name "unconnected-(U6-Vref-Pad5)") (class "Default")
      (node (ref "U6") (pin "5") (pinfunction "Vref_5") (pintype "passive"))
    )
  )
)
